# CurrentSensor.net
KiCad netlist of a schematic drawn in Altium Designer
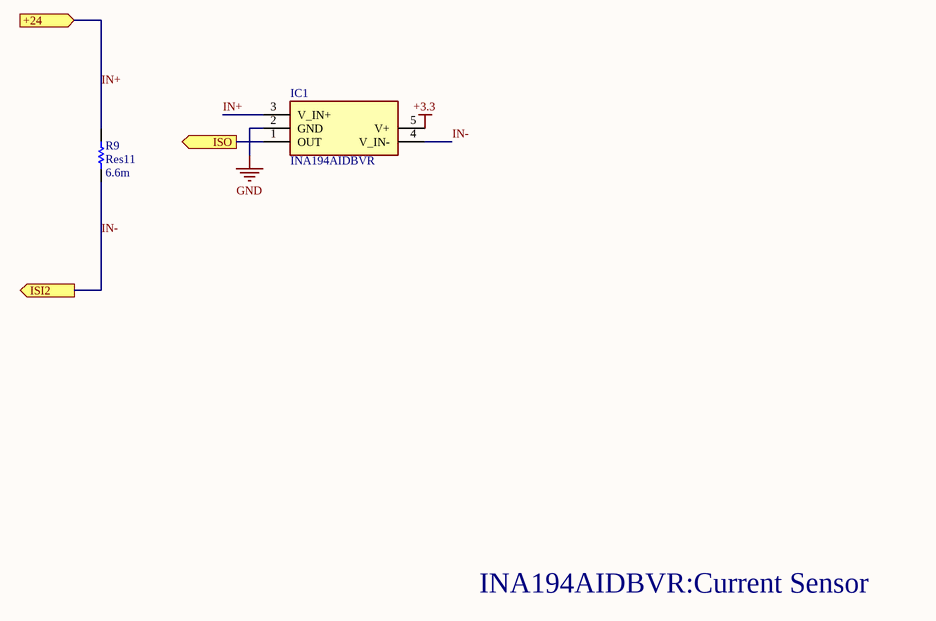
[diagram p0: CurrentSensor.SchDoc]

(export (version "E")
  (design (tool "Eeschema 10.0.6"))
  (components
    (comp (ref "IC1")
      (value "INA194AIDBVR")
      (footprint "SOT95P280X145-5N")
      (description "Integrated Circuit")
      (fields (field (name "MOUSER PART NUMBER") "595-INA194AIDBVR"))
      (libsource (lib "*") (part "INA194AIDBVR"))
    )
    (comp (ref "R9")
      (value "Res11")
      (footprint "0402")
      (description "Resistor")
      (fields (field (name "ALTIUM_VALUE") "6.6m") (field (name "PUBLISHER") "Altium Limited"))
      (libsource (lib "Miscellaneous Devices") (part "Res1"))
    )
  )
  (nets
    (net (code "1") (name "+3.3") (class "Default")
      (node (ref "IC1") (pin "5") (pinfunction "V+_5") (pintype "passive"))
    )
    (net (code "2") (name "/IN+") (class "Default")
      (node (ref "IC1") (pin "3") (pinfunction "V_IN+_3") (pintype "passive"))
      (node (ref "R9") (pin "2") (pinfunction "2_2") (pintype "passive"))
    )
    (net (code "3") (name "/IN-") (class "Default")
      (node (ref "IC1") (pin "4") (pinfunction "V_IN-_4") (pintype "passive"))
      (node (ref "R9") (pin "1") (pinfunction "1_1") (pintype "passive"))
    )
    (net (code "4") (name "/ISO") (class "Default")
      (node (ref "IC1") (pin "1") (pinfunction "OUT_1") (pintype "passive"))
    )
    (net (code "5") (name "GND") (class "Default")
      (node (ref "IC1") (pin "2") (pinfunction "GND_2") (pintype "passive"))
    )
  )
)
